# Slave.net
KiCad netlist of a schematic drawn in Altium Designer
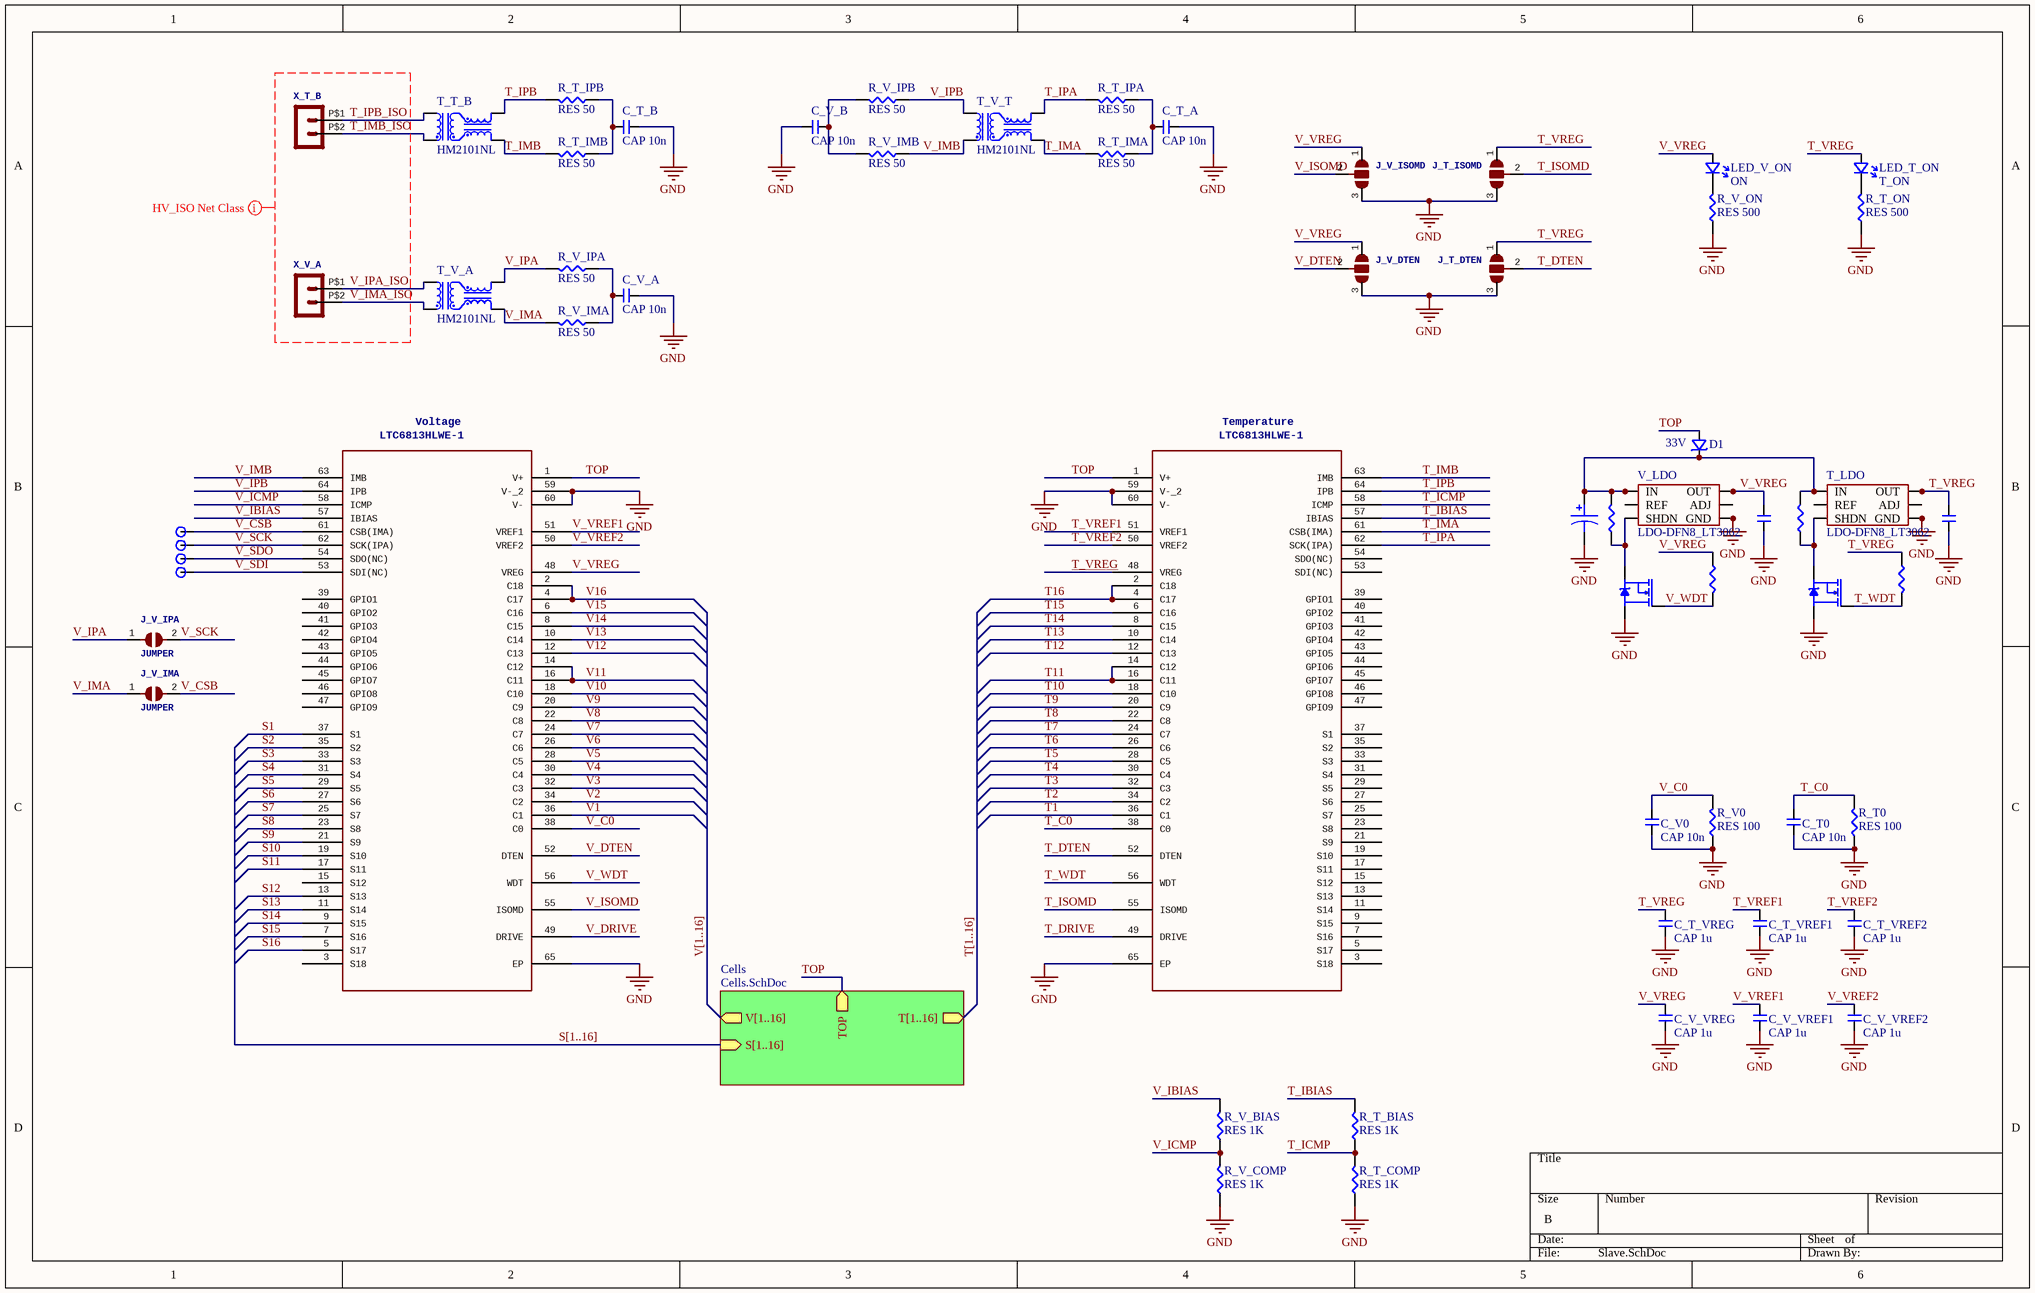
[diagram p0: Slave.SchDoc]

(export (version "E")
  (design (tool "Eeschema 10.0.6"))
  (components
    (comp (ref "CAP-T_VREG")
      (value "10uF")
      (footprint "CAP-0603")
      (libsource (lib "ife19_Elec_Library") (part "CAP-0603"))
    )
    (comp (ref "CAP-V_VREG")
      (value "10uF")
      (footprint "CAP-0603")
      (libsource (lib "ife19_Elec_Library") (part "CAP-0603"))
    )
    (comp (ref "CAP_TOP")
      (value "10uF")
      (footprint "CAP-6.3D7.7H-SMD")
      (libsource (lib "ife19_Elec_Library") (part "CAP-6.3D7.7H-SMD"))
    )
    (comp (ref "C_T0")
      (value "CAP 10n")
      (footprint "CAP-0603")
      (description "CAP-0603")
      (libsource (lib "altium-import") (part "root_1_CAP-0603_"))
    )
    (comp (ref "C_T_A")
      (value "CAP 10n")
      (footprint "CAP-0603")
      (description "CAP-0603")
      (libsource (lib "ife18_TS_BMS_LTC6813_v2_Library") (part "CAP-0603"))
    )
    (comp (ref "C_T_B")
      (value "CAP 10n")
      (footprint "CAP-0603")
      (description "CAP-0603")
      (libsource (lib "ife18_TS_BMS_LTC6813_v2_Library") (part "CAP-0603"))
    )
    (comp (ref "C_T_VREF1")
      (value "CAP 1u")
      (footprint "CAP-0603")
      (description "CAP-0603")
      (libsource (lib "altium-import") (part "root_1_CAP-0603_"))
    )
    (comp (ref "C_T_VREF2")
      (value "CAP 1u")
      (footprint "CAP-0603")
      (description "CAP-0603")
      (libsource (lib "altium-import") (part "root_1_CAP-0603_"))
    )
    (comp (ref "C_T_VREG")
      (value "CAP 1u")
      (footprint "CAP-0603")
      (description "CAP-0603")
      (libsource (lib "altium-import") (part "root_1_CAP-0603_"))
    )
    (comp (ref "C_V0")
      (value "CAP 10n")
      (footprint "CAP-0603")
      (description "CAP-0603")
      (libsource (lib "altium-import") (part "root_1_CAP-0603_"))
    )
    (comp (ref "C_V_A")
      (value "CAP 10n")
      (footprint "CAP-0603")
      (description "CAP-0603")
      (libsource (lib "ife18_TS_BMS_LTC6813_v2_Library") (part "CAP-0603"))
    )
    (comp (ref "C_V_B")
      (value "CAP 10n")
      (footprint "CAP-0603")
      (description "CAP-0603")
      (libsource (lib "ife18_TS_BMS_LTC6813_v2_Library") (part "CAP-0603"))
    )
    (comp (ref "C_V_VREF1")
      (value "CAP 1u")
      (footprint "CAP-0603")
      (description "CAP-0603")
      (libsource (lib "altium-import") (part "root_1_CAP-0603_"))
    )
    (comp (ref "C_V_VREF2")
      (value "CAP 1u")
      (footprint "CAP-0603")
      (description "CAP-0603")
      (libsource (lib "altium-import") (part "root_1_CAP-0603_"))
    )
    (comp (ref "C_V_VREG")
      (value "CAP 1u")
      (footprint "CAP-0603")
      (description "CAP-0603")
      (libsource (lib "altium-import") (part "root_1_CAP-0603_"))
    )
    (comp (ref "D1")
      (value "33V")
      (footprint "SMB")
      (libsource (lib "ife19_Elec_Library") (part "DIODE-SMB"))
    )
    (comp (ref "J_T_DTEN")
      (value "~")
      (footprint "SJ_2")
      (description "JUMPER_2W")
      (libsource (lib "") (part "JUMPER_2W_1"))
    )
    (comp (ref "J_T_ISOMD")
      (value "~")
      (footprint "SJ_2")
      (description "JUMPER_2W")
      (libsource (lib "") (part "JUMPER_2W_1"))
    )
    (comp (ref "J_V_DTEN")
      (value "~")
      (footprint "SJ_2")
      (description "JUMPER_2W")
      (libsource (lib "IFE_Jumpers") (part "JUMPER_2W"))
    )
    (comp (ref "J_V_IMA")
      (value "JUMPER")
      (footprint "SJ")
      (libsource (lib "altium-import") (part "root_0_JUMPER_"))
    )
    (comp (ref "J_V_IPA")
      (value "JUMPER")
      (footprint "SJ")
      (libsource (lib "altium-import") (part "root_0_JUMPER_"))
    )
    (comp (ref "J_V_ISOMD")
      (value "~")
      (footprint "SJ_2")
      (description "JUMPER_2W")
      (libsource (lib "IFE_Jumpers") (part "JUMPER_2W"))
    )
    (comp (ref "LED_T_ON")
      (value "T_ON")
      (footprint "LED-0603")
      (description "LED-0603")
      (libsource (lib "altium-import") (part "root_3_LED-0603_"))
    )
    (comp (ref "LED_V_ON")
      (value "ON")
      (footprint "LED-0603")
      (description "LED-0603")
      (libsource (lib "altium-import") (part "root_3_LED-0603_"))
    )
    (comp (ref "R_T0")
      (value "RES 100")
      (footprint "RES-0603")
      (libsource (lib "altium-import") (part "root_1_RES-0603_"))
    )
    (comp (ref "R_T_BIAS")
      (value "RES 1K")
      (footprint "RES-0603")
      (libsource (lib "altium-import") (part "root_1_RES-0603_"))
    )
    (comp (ref "R_T_COMP")
      (value "RES 1K")
      (footprint "RES-0603")
      (libsource (lib "altium-import") (part "root_1_RES-0603_"))
    )
    (comp (ref "R_T_IMA")
      (value "RES 50")
      (footprint "RES-0603")
      (libsource (lib "ife18_TS_BMS_LTC6813_v2_Library") (part "RES-0603"))
    )
    (comp (ref "R_T_IMB")
      (value "RES 50")
      (footprint "RES-0603")
      (libsource (lib "ife18_TS_BMS_LTC6813_v2_Library") (part "RES-0603"))
    )
    (comp (ref "R_T_IPA")
      (value "RES 50")
      (footprint "RES-0603")
      (libsource (lib "ife18_TS_BMS_LTC6813_v2_Library") (part "RES-0603"))
    )
    (comp (ref "R_T_IPB")
      (value "RES 50")
      (footprint "RES-0603")
      (libsource (lib "ife18_TS_BMS_LTC6813_v2_Library") (part "RES-0603"))
    )
    (comp (ref "R_T_ON")
      (value "RES 500")
      (footprint "RES-0603")
      (libsource (lib "altium-import") (part "root_1_RES-0603_"))
    )
    (comp (ref "R_V0")
      (value "RES 100")
      (footprint "RES-0603")
      (libsource (lib "altium-import") (part "root_1_RES-0603_"))
    )
    (comp (ref "R_V_BIAS")
      (value "RES 1K")
      (footprint "RES-0603")
      (libsource (lib "altium-import") (part "root_1_RES-0603_"))
    )
    (comp (ref "R_V_COMP")
      (value "RES 1K")
      (footprint "RES-0603")
      (libsource (lib "altium-import") (part "root_1_RES-0603_"))
    )
    (comp (ref "R_V_IMA")
      (value "RES 50")
      (footprint "RES-0603")
      (libsource (lib "ife18_TS_BMS_LTC6813_v2_Library") (part "RES-0603"))
    )
    (comp (ref "R_V_IMB")
      (value "RES 50")
      (footprint "RES-0603")
      (libsource (lib "ife18_TS_BMS_LTC6813_v2_Library") (part "RES-0603"))
    )
    (comp (ref "R_V_IPA")
      (value "RES 50")
      (footprint "RES-0603")
      (libsource (lib "ife18_TS_BMS_LTC6813_v2_Library") (part "RES-0603"))
    )
    (comp (ref "R_V_IPB")
      (value "RES 50")
      (footprint "RES-0603")
      (libsource (lib "ife18_TS_BMS_LTC6813_v2_Library") (part "RES-0603"))
    )
    (comp (ref "R_V_ON")
      (value "RES 500")
      (footprint "RES-0603")
      (libsource (lib "altium-import") (part "root_1_RES-0603_"))
    )
    (comp (ref "Temperature")
      (value "LTC6813HLWE-1")
      (footprint "LQFP64_LWE_A")
      (fields (field (name "LIBRARYNAME") "LTC6813_Official"))
      (libsource (lib "altium-import") (part "root_0_LTC6813HLWE-1_"))
    )
    (comp (ref "TP_CSB")
      (value "S")
      (footprint "Testpoint")
      (libsource (lib "altium-import") (part "root_0_Testpoint_"))
    )
    (comp (ref "TP_SCK")
      (value "C")
      (footprint "Testpoint")
      (libsource (lib "altium-import") (part "root_0_Testpoint_"))
    )
    (comp (ref "TP_SDI")
      (value "I")
      (footprint "Testpoint")
      (libsource (lib "altium-import") (part "root_0_Testpoint_"))
    )
    (comp (ref "TP_SDO")
      (value "O")
      (footprint "Testpoint")
      (libsource (lib "altium-import") (part "root_0_Testpoint_"))
    )
    (comp (ref "T_LDO")
      (value "LDO-DFN8_LT3062")
      (footprint "DFN8")
      (libsource (lib "ife19_Elec_Library") (part "LDO-DFN8_LT3062"))
    )
    (comp (ref "T_LDO_NMOS")
      (value "NMOS-SOT23")
      (footprint "SOT23")
      (libsource (lib "ife19_Elec_Library") (part "NMOS-SOT23"))
    )
    (comp (ref "T_LDO_NMOS_PU")
      (value "100K")
      (footprint "RES-0603")
      (libsource (lib "ife19_Elec_Library") (part "RES-0603"))
    )
    (comp (ref "T_LDO_PU")
      (value "10K")
      (footprint "RES-0603")
      (libsource (lib "ife19_Elec_Library") (part "RES-0603"))
    )
    (comp (ref "T_T_B")
      (value "HM2101NL")
      (footprint "HM2101")
      (libsource (lib "altium-import") (part "root_2_HM2101NL_"))
    )
    (comp (ref "T_V_A")
      (value "HM2101NL")
      (footprint "HM2101")
      (libsource (lib "altium-import") (part "root_2_HM2101NL_"))
    )
    (comp (ref "T_V_T")
      (value "HM2101NL")
      (footprint "HM2101")
      (libsource (lib "altium-import") (part "root_2_HM2101NL_"))
    )
    (comp (ref "Voltage")
      (value "LTC6813HLWE-1")
      (footprint "LQFP64_LWE_A")
      (fields (field (name "LIBRARYNAME") "LTC6813_Official"))
      (libsource (lib "altium-import") (part "root_0_mirrored_LTC6813HLWE-1_"))
    )
    (comp (ref "V_LDO")
      (value "LDO-DFN8_LT3062")
      (footprint "DFN8")
      (libsource (lib "ife19_Elec_Library") (part "LDO-DFN8_LT3062"))
    )
    (comp (ref "V_LDO_NMOS")
      (value "NMOS-SOT23")
      (footprint "SOT23")
      (libsource (lib "ife19_Elec_Library") (part "NMOS-SOT23"))
    )
    (comp (ref "V_LDO_NMOS_PU")
      (value "100K")
      (footprint "RES-0603")
      (libsource (lib "ife19_Elec_Library") (part "RES-0603"))
    )
    (comp (ref "V_LDO_PU")
      (value "10K")
      (footprint "RES-0603")
      (libsource (lib "ife19_Elec_Library") (part "RES-0603"))
    )
    (comp (ref "X_T_B")
      (value "Molex - Micro-Fit 3.0 Series connector,  3.00mm (0.118\") pitch header, 2 positions.")
      (footprint "43650-0224")
      (libsource (lib "altium-import") (part "root_0_mirrored_HEADER_POS2_?43650-0224_"))
    )
    (comp (ref "X_V_A")
      (value "Molex - Micro-Fit 3.0 Series connector,  3.00mm (0.118\") pitch header, 2 positions.")
      (footprint "43650-0224")
      (libsource (lib "altium-import") (part "root_0_mirrored_HEADER_POS2_?43650-0224_"))
    )
  )
  (nets
    (net (code "1") (name "/S1") (class "Default")
      (node (ref "Voltage") (pin "37") (pinfunction "S1_37") (pintype "passive"))
    )
    (net (code "2") (name "/S2") (class "Default")
      (node (ref "Voltage") (pin "35") (pinfunction "S2_35") (pintype "passive"))
    )
    (net (code "3") (name "/S3") (class "Default")
      (node (ref "Voltage") (pin "33") (pinfunction "S3_33") (pintype "passive"))
    )
    (net (code "4") (name "/S4") (class "Default")
      (node (ref "Voltage") (pin "31") (pinfunction "S4_31") (pintype "passive"))
    )
    (net (code "5") (name "/S5") (class "Default")
      (node (ref "Voltage") (pin "29") (pinfunction "S5_29") (pintype "passive"))
    )
    (net (code "6") (name "/S6") (class "Default")
      (node (ref "Voltage") (pin "27") (pinfunction "S6_27") (pintype "passive"))
    )
    (net (code "7") (name "/S7") (class "Default")
      (node (ref "Voltage") (pin "25") (pinfunction "S7_25") (pintype "passive"))
    )
    (net (code "8") (name "/S8") (class "Default")
      (node (ref "Voltage") (pin "23") (pinfunction "S8_23") (pintype "passive"))
    )
    (net (code "9") (name "/S9") (class "Default")
      (node (ref "Voltage") (pin "21") (pinfunction "S9_21") (pintype "passive"))
    )
    (net (code "10") (name "/S10") (class "Default")
      (node (ref "Voltage") (pin "19") (pinfunction "S10_19") (pintype "passive"))
    )
    (net (code "11") (name "/S11") (class "Default")
      (node (ref "Voltage") (pin "17") (pinfunction "S11_17") (pintype "passive"))
    )
    (net (code "12") (name "/S12") (class "Default")
      (node (ref "Voltage") (pin "13") (pinfunction "S13_13") (pintype "passive"))
    )
    (net (code "13") (name "/S13") (class "Default")
      (node (ref "Voltage") (pin "11") (pinfunction "S14_11") (pintype "passive"))
    )
    (net (code "14") (name "/S14") (class "Default")
      (node (ref "Voltage") (pin "9") (pinfunction "S15_9") (pintype "passive"))
    )
    (net (code "15") (name "/S15") (class "Default")
      (node (ref "Voltage") (pin "7") (pinfunction "S16_7") (pintype "passive"))
    )
    (net (code "16") (name "/S16") (class "Default")
      (node (ref "Voltage") (pin "5") (pinfunction "S17_5") (pintype "passive"))
    )
    (net (code "18") (name "/T1") (class "Default")
      (node (ref "Temperature") (pin "36") (pinfunction "C1_36") (pintype "passive"))
    )
    (net (code "19") (name "/T2") (class "Default")
      (node (ref "Temperature") (pin "34") (pinfunction "C2_34") (pintype "passive"))
    )
    (net (code "20") (name "/T3") (class "Default")
      (node (ref "Temperature") (pin "32") (pinfunction "C3_32") (pintype "passive"))
    )
    (net (code "21") (name "/T4") (class "Default")
      (node (ref "Temperature") (pin "30") (pinfunction "C4_30") (pintype "passive"))
    )
    (net (code "22") (name "/T5") (class "Default")
      (node (ref "Temperature") (pin "28") (pinfunction "C5_28") (pintype "passive"))
    )
    (net (code "23") (name "/T6") (class "Default")
      (node (ref "Temperature") (pin "26") (pinfunction "C6_26") (pintype "passive"))
    )
    (net (code "24") (name "/T7") (class "Default")
      (node (ref "Temperature") (pin "24") (pinfunction "C7_24") (pintype "passive"))
    )
    (net (code "25") (name "/T8") (class "Default")
      (node (ref "Temperature") (pin "22") (pinfunction "C8_22") (pintype "passive"))
    )
    (net (code "26") (name "/T9") (class "Default")
      (node (ref "Temperature") (pin "20") (pinfunction "C9_20") (pintype "passive"))
    )
    (net (code "27") (name "/T10") (class "Default")
      (node (ref "Temperature") (pin "18") (pinfunction "C10_18") (pintype "passive"))
    )
    (net (code "28") (name "/T11") (class "Default")
      (node (ref "Temperature") (pin "14") (pinfunction "C12_14") (pintype "passive"))
      (node (ref "Temperature") (pin "16") (pinfunction "C11_16") (pintype "passive"))
    )
    (net (code "29") (name "/T12") (class "Default")
      (node (ref "Temperature") (pin "12") (pinfunction "C13_12") (pintype "passive"))
    )
    (net (code "30") (name "/T13") (class "Default")
      (node (ref "Temperature") (pin "10") (pinfunction "C14_10") (pintype "passive"))
    )
    (net (code "31") (name "/T14") (class "Default")
      (node (ref "Temperature") (pin "8") (pinfunction "C15_8") (pintype "passive"))
    )
    (net (code "32") (name "/T15") (class "Default")
      (node (ref "Temperature") (pin "6") (pinfunction "C16_6") (pintype "passive"))
    )
    (net (code "33") (name "/T16") (class "Default")
      (node (ref "Temperature") (pin "2") (pinfunction "C18_2") (pintype "passive"))
      (node (ref "Temperature") (pin "4") (pinfunction "C17_4") (pintype "passive"))
    )
    (net (code "34") (name "/TOP") (class "Default")
      (node (ref "D1") (pin "A") (pinfunction "A_A") (pintype "passive"))
      (node (ref "Temperature") (pin "1") (pinfunction "V+_1") (pintype "passive"))
      (node (ref "Voltage") (pin "1") (pinfunction "V+_1") (pintype "passive"))
    )
    (net (code "36") (name "/T_C0") (class "Default")
      (node (ref "C_T0") (pin "2") (pinfunction "2_2") (pintype "passive"))
      (node (ref "R_T0") (pin "2") (pinfunction "2_2") (pintype "passive"))
      (node (ref "Temperature") (pin "38") (pinfunction "C0_38") (pintype "passive"))
    )
    (net (code "37") (name "/T_DRIVE") (class "Default")
      (node (ref "Temperature") (pin "49") (pinfunction "DRIVE_49") (pintype "passive"))
    )
    (net (code "38") (name "/T_DTEN") (class "Default")
      (node (ref "J_T_DTEN") (pin "2") (pinfunction "2_2") (pintype "passive"))
      (node (ref "Temperature") (pin "52") (pinfunction "DTEN_52") (pintype "passive"))
    )
    (net (code "39") (name "/T_IBIAS") (class "Default")
      (node (ref "R_T_BIAS") (pin "2") (pinfunction "2_2") (pintype "passive"))
      (node (ref "Temperature") (pin "57") (pinfunction "IBIAS_57") (pintype "passive"))
    )
    (net (code "40") (name "/T_ICMP") (class "Default")
      (node (ref "R_T_BIAS") (pin "1") (pinfunction "1_1") (pintype "passive"))
      (node (ref "R_T_COMP") (pin "2") (pinfunction "2_2") (pintype "passive"))
      (node (ref "Temperature") (pin "58") (pinfunction "ICMP_58") (pintype "passive"))
    )
    (net (code "41") (name "/T_IMA") (class "Default")
      (node (ref "R_T_IMA") (pin "2") (pinfunction "2_2") (pintype "passive"))
      (node (ref "T_V_T") (pin "4") (pinfunction "4_4") (pintype "passive"))
      (node (ref "Temperature") (pin "61") (pinfunction "CSB(IMA)_61") (pintype "passive"))
    )
    (net (code "42") (name "/T_IMB") (class "Default")
      (node (ref "R_T_IMB") (pin "2") (pinfunction "2_2") (pintype "passive"))
      (node (ref "T_T_B") (pin "4") (pinfunction "4_4") (pintype "passive"))
      (node (ref "Temperature") (pin "63") (pinfunction "IMB_63") (pintype "passive"))
    )
    (net (code "43") (name "/T_IMB_ISO") (class "Default")
      (node (ref "T_T_B") (pin "3") (pinfunction "3_3") (pintype "passive"))
      (node (ref "X_T_B") (pin "P$2") (pinfunction "2_P$2") (pintype "passive"))
    )
    (net (code "44") (name "/T_IPA") (class "Default")
      (node (ref "R_T_IPA") (pin "2") (pinfunction "2_2") (pintype "passive"))
      (node (ref "T_V_T") (pin "6") (pinfunction "6_6") (pintype "passive"))
      (node (ref "Temperature") (pin "62") (pinfunction "SCK(IPA)_62") (pintype "passive"))
    )
    (net (code "45") (name "/T_IPB") (class "Default")
      (node (ref "R_T_IPB") (pin "2") (pinfunction "2_2") (pintype "passive"))
      (node (ref "T_T_B") (pin "6") (pinfunction "6_6") (pintype "passive"))
      (node (ref "Temperature") (pin "64") (pinfunction "IPB_64") (pintype "passive"))
    )
    (net (code "46") (name "/T_IPB_ISO") (class "Default")
      (node (ref "T_T_B") (pin "1") (pinfunction "1_1") (pintype "passive"))
      (node (ref "X_T_B") (pin "P$1") (pinfunction "1_P$1") (pintype "passive"))
    )
    (net (code "47") (name "/T_ISOMD") (class "Default")
      (node (ref "J_T_ISOMD") (pin "2") (pinfunction "2_2") (pintype "passive"))
      (node (ref "Temperature") (pin "55") (pinfunction "ISOMD_55") (pintype "passive"))
    )
    (net (code "48") (name "/T_VREF1") (class "Default")
      (node (ref "C_T_VREF1") (pin "2") (pinfunction "2_2") (pintype "passive"))
      (node (ref "Temperature") (pin "51") (pinfunction "VREF1_51") (pintype "passive"))
    )
    (net (code "49") (name "/T_VREF2") (class "Default")
      (node (ref "C_T_VREF2") (pin "2") (pinfunction "2_2") (pintype "passive"))
      (node (ref "Temperature") (pin "50") (pinfunction "VREF2_50") (pintype "passive"))
    )
    (net (code "50") (name "/T_VREG") (class "Default")
      (node (ref "CAP-T_VREG") (pin "2") (pinfunction "2_2") (pintype "passive"))
      (node (ref "C_T_VREG") (pin "2") (pinfunction "2_2") (pintype "passive"))
      (node (ref "J_T_DTEN") (pin "1") (pinfunction "1_1") (pintype "passive"))
      (node (ref "J_T_ISOMD") (pin "1") (pinfunction "1_1") (pintype "passive"))
      (node (ref "LED_T_ON") (pin "A") (pinfunction "A_A") (pintype "passive"))
      (node (ref "T_LDO") (pin "3") (pinfunction "OUT_3") (pintype "passive"))
      (node (ref "T_LDO") (pin "4") (pinfunction "OUT_4") (pintype "passive"))
      (node (ref "T_LDO_NMOS_PU") (pin "1") (pinfunction "1_1") (pintype "passive"))
      (node (ref "Temperature") (pin "48") (pinfunction "VREG_48") (pintype "passive"))
    )
    (net (code "51") (name "/T_WDT") (class "Default")
      (node (ref "T_LDO_NMOS") (pin "1") (pinfunction "G_1") (pintype "passive"))
      (node (ref "T_LDO_NMOS_PU") (pin "2") (pinfunction "2_2") (pintype "passive"))
      (node (ref "Temperature") (pin "56") (pinfunction "WDT_56") (pintype "passive"))
    )
    (net (code "52") (name "/V1") (class "Default")
      (node (ref "Voltage") (pin "36") (pinfunction "C1_36") (pintype "passive"))
    )
    (net (code "53") (name "/V2") (class "Default")
      (node (ref "Voltage") (pin "34") (pinfunction "C2_34") (pintype "passive"))
    )
    (net (code "54") (name "/V3") (class "Default")
      (node (ref "Voltage") (pin "32") (pinfunction "C3_32") (pintype "passive"))
    )
    (net (code "55") (name "/V4") (class "Default")
      (node (ref "Voltage") (pin "30") (pinfunction "C4_30") (pintype "passive"))
    )
    (net (code "56") (name "/V5") (class "Default")
      (node (ref "Voltage") (pin "28") (pinfunction "C5_28") (pintype "passive"))
    )
    (net (code "57") (name "/V6") (class "Default")
      (node (ref "Voltage") (pin "26") (pinfunction "C6_26") (pintype "passive"))
    )
    (net (code "58") (name "/V7") (class "Default")
      (node (ref "Voltage") (pin "24") (pinfunction "C7_24") (pintype "passive"))
    )
    (net (code "59") (name "/V8") (class "Default")
      (node (ref "Voltage") (pin "22") (pinfunction "C8_22") (pintype "passive"))
    )
    (net (code "60") (name "/V9") (class "Default")
      (node (ref "Voltage") (pin "20") (pinfunction "C9_20") (pintype "passive"))
    )
    (net (code "61") (name "/V10") (class "Default")
      (node (ref "Voltage") (pin "18") (pinfunction "C10_18") (pintype "passive"))
    )
    (net (code "62") (name "/V11") (class "Default")
      (node (ref "Voltage") (pin "14") (pinfunction "C12_14") (pintype "passive"))
      (node (ref "Voltage") (pin "16") (pinfunction "C11_16") (pintype "passive"))
    )
    (net (code "63") (name "/V12") (class "Default")
      (node (ref "Voltage") (pin "12") (pinfunction "C13_12") (pintype "passive"))
    )
    (net (code "64") (name "/V13") (class "Default")
      (node (ref "Voltage") (pin "10") (pinfunction "C14_10") (pintype "passive"))
    )
    (net (code "65") (name "/V14") (class "Default")
      (node (ref "Voltage") (pin "8") (pinfunction "C15_8") (pintype "passive"))
    )
    (net (code "66") (name "/V15") (class "Default")
      (node (ref "Voltage") (pin "6") (pinfunction "C16_6") (pintype "passive"))
    )
    (net (code "67") (name "/V16") (class "Default")
      (node (ref "Voltage") (pin "2") (pinfunction "C18_2") (pintype "passive"))
      (node (ref "Voltage") (pin "4") (pinfunction "C17_4") (pintype "passive"))
    )
    (net (code "69") (name "/V_C0") (class "Default")
      (node (ref "C_V0") (pin "2") (pinfunction "2_2") (pintype "passive"))
      (node (ref "R_V0") (pin "2") (pinfunction "2_2") (pintype "passive"))
      (node (ref "Voltage") (pin "38") (pinfunction "C0_38") (pintype "passive"))
    )
    (net (code "70") (name "/V_CSB") (class "Default")
      (node (ref "J_V_IMA") (pin "2") (pinfunction "2_2") (pintype "passive"))
      (node (ref "TP_CSB") (pin "1") (pinfunction "1_1") (pintype "passive"))
      (node (ref "Voltage") (pin "61") (pinfunction "CSB(IMA)_61") (pintype "passive"))
    )
    (net (code "71") (name "/V_DRIVE") (class "Default")
      (node (ref "Voltage") (pin "49") (pinfunction "DRIVE_49") (pintype "passive"))
    )
    (net (code "72") (name "/V_DTEN") (class "Default")
      (node (ref "J_V_DTEN") (pin "2") (pinfunction "2_2") (pintype "passive"))
      (node (ref "Voltage") (pin "52") (pinfunction "DTEN_52") (pintype "passive"))
    )
    (net (code "73") (name "/V_IBIAS") (class "Default")
      (node (ref "R_V_BIAS") (pin "2") (pinfunction "2_2") (pintype "passive"))
      (node (ref "Voltage") (pin "57") (pinfunction "IBIAS_57") (pintype "passive"))
    )
    (net (code "74") (name "/V_ICMP") (class "Default")
      (node (ref "R_V_BIAS") (pin "1") (pinfunction "1_1") (pintype "passive"))
      (node (ref "R_V_COMP") (pin "2") (pinfunction "2_2") (pintype "passive"))
      (node (ref "Voltage") (pin "58") (pinfunction "ICMP_58") (pintype "passive"))
    )
    (net (code "75") (name "/V_IMA") (class "Default")
      (node (ref "J_V_IMA") (pin "1") (pinfunction "1_1") (pintype "passive"))
      (node (ref "R_V_IMA") (pin "2") (pinfunction "2_2") (pintype "passive"))
      (node (ref "T_V_A") (pin "4") (pinfunction "4_4") (pintype "passive"))
    )
    (net (code "76") (name "/V_IMA_ISO") (class "Default")
      (node (ref "T_V_A") (pin "3") (pinfunction "3_3") (pintype "passive"))
      (node (ref "X_V_A") (pin "P$2") (pinfunction "2_P$2") (pintype "passive"))
    )
    (net (code "77") (name "/V_IMB") (class "Default")
      (node (ref "R_V_IMB") (pin "2") (pinfunction "2_2") (pintype "passive"))
      (node (ref "T_V_T") (pin "3") (pinfunction "3_3") (pintype "passive"))
      (node (ref "Voltage") (pin "63") (pinfunction "IMB_63") (pintype "passive"))
    )
    (net (code "78") (name "/V_IPA") (class "Default")
      (node (ref "J_V_IPA") (pin "1") (pinfunction "1_1") (pintype "passive"))
      (node (ref "R_V_IPA") (pin "2") (pinfunction "2_2") (pintype "passive"))
      (node (ref "T_V_A") (pin "6") (pinfunction "6_6") (pintype "passive"))
    )
    (net (code "79") (name "/V_IPA_ISO") (class "Default")
      (node (ref "T_V_A") (pin "1") (pinfunction "1_1") (pintype "passive"))
      (node (ref "X_V_A") (pin "P$1") (pinfunction "1_P$1") (pintype "passive"))
    )
    (net (code "80") (name "/V_IPB") (class "Default")
      (node (ref "R_V_IPB") (pin "2") (pinfunction "2_2") (pintype "passive"))
      (node (ref "T_V_T") (pin "1") (pinfunction "1_1") (pintype "passive"))
      (node (ref "Voltage") (pin "64") (pinfunction "IPB_64") (pintype "passive"))
    )
    (net (code "81") (name "/V_ISOMD") (class "Default")
      (node (ref "J_V_ISOMD") (pin "2") (pinfunction "2_2") (pintype "passive"))
      (node (ref "Voltage") (pin "55") (pinfunction "ISOMD_55") (pintype "passive"))
    )
    (net (code "82") (name "/V_SCK") (class "Default")
      (node (ref "J_V_IPA") (pin "2") (pinfunction "2_2") (pintype "passive"))
      (node (ref "TP_SCK") (pin "1") (pinfunction "1_1") (pintype "passive"))
      (node (ref "Voltage") (pin "62") (pinfunction "SCK(IPA)_62") (pintype "passive"))
    )
    (net (code "83") (name "/V_SDI") (class "Default")
      (node (ref "TP_SDI") (pin "1") (pinfunction "1_1") (pintype "passive"))
      (node (ref "Voltage") (pin "53") (pinfunction "SDI(NC)_53") (pintype "passive"))
    )
    (net (code "84") (name "/V_SDO") (class "Default")
      (node (ref "TP_SDO") (pin "1") (pinfunction "1_1") (pintype "passive"))
      (node (ref "Voltage") (pin "54") (pinfunction "SDO(NC)_54") (pintype "passive"))
    )
    (net (code "85") (name "/V_VREF1") (class "Default")
      (node (ref "C_V_VREF1") (pin "2") (pinfunction "2_2") (pintype "passive"))
      (node (ref "Voltage") (pin "51") (pinfunction "VREF1_51") (pintype "passive"))
    )
    (net (code "86") (name "/V_VREF2") (class "Default")
      (node (ref "C_V_VREF2") (pin "2") (pinfunction "2_2") (pintype "passive"))
      (node (ref "Voltage") (pin "50") (pinfunction "VREF2_50") (pintype "passive"))
    )
    (net (code "87") (name "/V_VREG") (class "Default")
      (node (ref "CAP-V_VREG") (pin "2") (pinfunction "2_2") (pintype "passive"))
      (node (ref "C_V_VREG") (pin "2") (pinfunction "2_2") (pintype "passive"))
      (node (ref "J_V_DTEN") (pin "1") (pinfunction "1_1") (pintype "passive"))
      (node (ref "J_V_ISOMD") (pin "1") (pinfunction "1_1") (pintype "passive"))
      (node (ref "LED_V_ON") (pin "A") (pinfunction "A_A") (pintype "passive"))
      (node (ref "V_LDO") (pin "3") (pinfunction "OUT_3") (pintype "passive"))
      (node (ref "V_LDO") (pin "4") (pinfunction "OUT_4") (pintype "passive"))
      (node (ref "V_LDO_NMOS_PU") (pin "1") (pinfunction "1_1") (pintype "passive"))
      (node (ref "Voltage") (pin "48") (pinfunction "VREG_48") (pintype "passive"))
    )
    (net (code "88") (name "/V_WDT") (class "Default")
      (node (ref "V_LDO_NMOS") (pin "1") (pinfunction "G_1") (pintype "passive"))
      (node (ref "V_LDO_NMOS_PU") (pin "2") (pinfunction "2_2") (pintype "passive"))
      (node (ref "Voltage") (pin "56") (pinfunction "WDT_56") (pintype "passive"))
    )
    (net (code "89") (name "GND") (class "Default")
      (node (ref "CAP-T_VREG") (pin "1") (pinfunction "1_1") (pintype "passive"))
      (node (ref "CAP-V_VREG") (pin "1") (pinfunction "1_1") (pintype "passive"))
      (node (ref "CAP_TOP") (pin "NEG") (pinfunction "-_NEG") (pintype "passive"))
      (node (ref "C_T0") (pin "1") (pinfunction "1_1") (pintype "passive"))
      (node (ref "C_T_A") (pin "1") (pinfunction "1_1") (pintype "passive"))
      (node (ref "C_T_B") (pin "1") (pinfunction "1_1") (pintype "passive"))
      (node (ref "C_T_VREF1") (pin "1") (pinfunction "1_1") (pintype "passive"))
      (node (ref "C_T_VREF2") (pin "1") (pinfunction "1_1") (pintype "passive"))
      (node (ref "C_T_VREG") (pin "1") (pinfunction "1_1") (pintype "passive"))
      (node (ref "C_V0") (pin "1") (pinfunction "1_1") (pintype "passive"))
      (node (ref "C_V_A") (pin "1") (pinfunction "1_1") (pintype "passive"))
      (node (ref "C_V_B") (pin "1") (pinfunction "1_1") (pintype "passive"))
      (node (ref "C_V_VREF1") (pin "1") (pinfunction "1_1") (pintype "passive"))
      (node (ref "C_V_VREF2") (pin "1") (pinfunction "1_1") (pintype "passive"))
      (node (ref "C_V_VREG") (pin "1") (pinfunction "1_1") (pintype "passive"))
      (node (ref "J_T_DTEN") (pin "3") (pinfunction "3_3") (pintype "passive"))
      (node (ref "J_T_ISOMD") (pin "3") (pinfunction "3_3") (pintype "passive"))
      (node (ref "J_V_DTEN") (pin "3") (pinfunction "3_3") (pintype "passive"))
      (node (ref "J_V_ISOMD") (pin "3") (pinfunction "3_3") (pintype "passive"))
      (node (ref "R_T0") (pin "1") (pinfunction "1_1") (pintype "passive"))
      (node (ref "R_T_COMP") (pin "1") (pinfunction "1_1") (pintype "passive"))
      (node (ref "R_T_ON") (pin "1") (pinfunction "1_1") (pintype "passive"))
      (node (ref "R_V0") (pin "1") (pinfunction "1_1") (pintype "passive"))
      (node (ref "R_V_COMP") (pin "1") (pinfunction "1_1") (pintype "passive"))
      (node (ref "R_V_ON") (pin "1") (pinfunction "1_1") (pintype "passive"))
      (node (ref "T_LDO") (pin "8") (pinfunction "GND_8") (pintype "passive"))
      (node (ref "T_LDO") (pin "EP") (pinfunction "GND_EP") (pintype "passive"))
      (node (ref "T_LDO_NMOS") (pin "2") (pinfunction "S_2") (pintype "passive"))
      (node (ref "Temperature") (pin "59") (pinfunction "V-_2_59") (pintype "passive"))
      (node (ref "Temperature") (pin "60") (pinfunction "V-_60") (pintype "passive"))
      (node (ref "Temperature") (pin "65") (pinfunction "EP_65") (pintype "passive"))
      (node (ref "V_LDO") (pin "8") (pinfunction "GND_8") (pintype "passive"))
      (node (ref "V_LDO") (pin "EP") (pinfunction "GND_EP") (pintype "passive"))
      (node (ref "V_LDO_NMOS") (pin "2") (pinfunction "S_2") (pintype "passive"))
      (node (ref "Voltage") (pin "59") (pinfunction "V-_2_59") (pintype "passive"))
      (node (ref "Voltage") (pin "60") (pinfunction "V-_60") (pintype "passive"))
      (node (ref "Voltage") (pin "65") (pinfunction "EP_65") (pintype "passive"))
    )
    (net (code "90") (name "Net-(CAP_TOP-+)") (class "Default")
      (node (ref "CAP_TOP") (pin "POS") (pinfunction "+_POS") (pintype "passive"))
      (node (ref "D1") (pin "K") (pinfunction "K_K") (pintype "passive"))
      (node (ref "T_LDO") (pin "5") (pinfunction "IN_5") (pintype "passive"))
      (node (ref "T_LDO") (pin "6") (pinfunction "IN_6") (pintype "passive"))
      (node (ref "T_LDO_PU") (pin "2") (pinfunction "2_2") (pintype "passive"))
      (node (ref "V_LDO") (pin "5") (pinfunction "IN_5") (pintype "passive"))
      (node (ref "V_LDO") (pin "6") (pinfunction "IN_6") (pintype "passive"))
      (node (ref "V_LDO_PU") (pin "2") (pinfunction "2_2") (pintype "passive"))
    )
    (net (code "91") (name "Net-(C_T_A-Pad2)") (class "Default")
      (node (ref "C_T_A") (pin "2") (pinfunction "2_2") (pintype "passive"))
      (node (ref "R_T_IMA") (pin "1") (pinfunction "1_1") (pintype "passive"))
      (node (ref "R_T_IPA") (pin "1") (pinfunction "1_1") (pintype "passive"))
    )
    (net (code "92") (name "Net-(C_T_B-Pad2)") (class "Default")
      (node (ref "C_T_B") (pin "2") (pinfunction "2_2") (pintype "passive"))
      (node (ref "R_T_IMB") (pin "1") (pinfunction "1_1") (pintype "passive"))
      (node (ref "R_T_IPB") (pin "1") (pinfunction "1_1") (pintype "passive"))
    )
    (net (code "93") (name "Net-(C_V_A-Pad2)") (class "Default")
      (node (ref "C_V_A") (pin "2") (pinfunction "2_2") (pintype "passive"))
      (node (ref "R_V_IMA") (pin "1") (pinfunction "1_1") (pintype "passive"))
      (node (ref "R_V_IPA") (pin "1") (pinfunction "1_1") (pintype "passive"))
    )
    (net (code "94") (name "Net-(C_V_B-Pad2)") (class "Default")
      (node (ref "C_V_B") (pin "2") (pinfunction "2_2") (pintype "passive"))
      (node (ref "R_V_IMB") (pin "1") (pinfunction "1_1") (pintype "passive"))
      (node (ref "R_V_IPB") (pin "1") (pinfunction "1_1") (pintype "passive"))
    )
    (net (code "95") (name "Net-(LED_T_ON-PadK)") (class "Default")
      (node (ref "LED_T_ON") (pin "K") (pinfunction "K_K") (pintype "passive"))
      (node (ref "R_T_ON") (pin "2") (pinfunction "2_2") (pintype "passive"))
    )
    (net (code "96") (name "Net-(LED_V_ON-PadK)") (class "Default")
      (node (ref "LED_V_ON") (pin "K") (pinfunction "K_K") (pintype "passive"))
      (node (ref "R_V_ON") (pin "2") (pinfunction "2_2") (pintype "passive"))
    )
    (net (code "97") (name "Net-(T_LDO-SHDN)") (class "Default")
      (node (ref "T_LDO") (pin "7") (pinfunction "SHDN_7") (pintype "passive"))
      (node (ref "T_LDO_NMOS") (pin "3") (pinfunction "D_3") (pintype "passive"))
      (node (ref "T_LDO_PU") (pin "1") (pinfunction "1_1") (pintype "passive"))
    )
    (net (code "98") (name "Net-(V_LDO-SHDN)") (class "Default")
      (node (ref "V_LDO") (pin "7") (pinfunction "SHDN_7") (pintype "passive"))
      (node (ref "V_LDO_NMOS") (pin "3") (pinfunction "D_3") (pintype "passive"))
      (node (ref "V_LDO_PU") (pin "1") (pinfunction "1_1") (pintype "passive"))
    )
    (net (code "99") (name "unconnected-(T_LDO-ADJ-Pad2)") (class "Default")
      (node (ref "T_LDO") (pin "2") (pinfunction "ADJ_2") (pintype "passive"))
    )
    (net (code "100") (name "unconnected-(T_LDO-REF-Pad1)") (class "Default")
      (node (ref "T_LDO") (pin "1") (pinfunction "REF_1") (pintype "passive"))
    )
    (net (code "101") (name "unconnected-(Temperature-GPIO1-Pad39)") (class "Default")
      (node (ref "Temperature") (pin "39") (pinfunction "GPIO1_39") (pintype "passive"))
    )
    (net (code "102") (name "unconnected-(Temperature-GPIO2-Pad40)") (class "Default")
      (node (ref "Temperature") (pin "40") (pinfunction "GPIO2_40") (pintype "passive"))
    )
    (net (code "103") (name "unconnected-(Temperature-GPIO3-Pad41)") (class "Default")
      (node (ref "Temperature") (pin "41") (pinfunction "GPIO3_41") (pintype "passive"))
    )
    (net (code "104") (name "unconnected-(Temperature-GPIO4-Pad42)") (class "Default")
      (node (ref "Temperature") (pin "42") (pinfunction "GPIO4_42") (pintype "passive"))
    )
    (net (code "105") (name "unconnected-(Temperature-GPIO5-Pad43)") (class "Default")
      (node (ref "Temperature") (pin "43") (pinfunction "GPIO5_43") (pintype "passive"))
    )
    (net (code "106") (name "unconnected-(Temperature-GPIO6-Pad44)") (class "Default")
      (node (ref "Temperature") (pin "44") (pinfunction "GPIO6_44") (pintype "passive"))
    )
    (net (code "107") (name "unconnected-(Temperature-GPIO7-Pad45)") (class "Default")
      (node (ref "Temperature") (pin "45") (pinfunction "GPIO7_45") (pintype "passive"))
    )
    (net (code "108") (name "unconnected-(Temperature-GPIO8-Pad46)") (class "Default")
      (node (ref "Temperature") (pin "46") (pinfunction "GPIO8_46") (pintype "passive"))
    )
    (net (code "109") (name "unconnected-(Temperature-GPIO9-Pad47)") (class "Default")
      (node (ref "Temperature") (pin "47") (pinfunction "GPIO9_47") (pintype "passive"))
    )
    (net (code "110") (name "unconnected-(Temperature-S1-Pad37)") (class "Default")
      (node (ref "Temperature") (pin "37") (pinfunction "S1_37") (pintype "passive"))
    )
    (net (code "111") (name "unconnected-(Temperature-S2-Pad35)") (class "Default")
      (node (ref "Temperature") (pin "35") (pinfunction "S2_35") (pintype "passive"))
    )
    (net (code "112") (name "unconnected-(Temperature-S3-Pad33)") (class "Default")
      (node (ref "Temperature") (pin "33") (pinfunction "S3_33") (pintype "passive"))
    )
    (net (code "113") (name "unconnected-(Temperature-S4-Pad31)") (class "Default")
      (node (ref "Temperature") (pin "31") (pinfunction "S4_31") (pintype "passive"))
    )
    (net (code "114") (name "unconnected-(Temperature-S5-Pad29)") (class "Default")
      (node (ref "Temperature") (pin "29") (pinfunction "S5_29") (pintype "passive"))
    )
    (net (code "115") (name "unconnected-(Temperature-S6-Pad27)") (class "Default")
      (node (ref "Temperature") (pin "27") (pinfunction "S6_27") (pintype "passive"))
    )
    (net (code "116") (name "unconnected-(Temperature-S7-Pad25)") (class "Default")
      (node (ref "Temperature") (pin "25") (pinfunction "S7_25") (pintype "passive"))
    )
    (net (code "117") (name "unconnected-(Temperature-S8-Pad23)") (class "Default")
      (node (ref "Temperature") (pin "23") (pinfunction "S8_23") (pintype "passive"))
    )
    (net (code "118") (name "unconnected-(Temperature-S9-Pad21)") (class "Default")
      (node (ref "Temperature") (pin "21") (pinfunction "S9_21") (pintype "passive"))
    )
    (net (code "119") (name "unconnected-(Temperature-S10-Pad19)") (class "Default")
      (node (ref "Temperature") (pin "19") (pinfunction "S10_19") (pintype "passive"))
    )
    (net (code "120") (name "unconnected-(Temperature-S11-Pad17)") (class "Default")
      (node (ref "Temperature") (pin "17") (pinfunction "S11_17") (pintype "passive"))
    )
    (net (code "121") (name "unconnected-(Temperature-S12-Pad15)") (class "Default")
      (node (ref "Temperature") (pin "15") (pinfunction "S12_15") (pintype "passive"))
    )
    (net (code "122") (name "unconnected-(Temperature-S13-Pad13)") (class "Default")
      (node (ref "Temperature") (pin "13") (pinfunction "S13_13") (pintype "passive"))
    )
    (net (code "123") (name "unconnected-(Temperature-S14-Pad11)") (class "Default")
      (node (ref "Temperature") (pin "11") (pinfunction "S14_11") (pintype "passive"))
    )
    (net (code "124") (name "unconnected-(Temperature-S15-Pad9)") (class "Default")
      (node (ref "Temperature") (pin "9") (pinfunction "S15_9") (pintype "passive"))
    )
    (net (code "125") (name "unconnected-(Temperature-S16-Pad7)") (class "Default")
      (node (ref "Temperature") (pin "7") (pinfunction "S16_7") (pintype "passive"))
    )
    (net (code "126") (name "unconnected-(Temperature-S17-Pad5)") (class "Default")
      (node (ref "Temperature") (pin "5") (pinfunction "S17_5") (pintype "passive"))
    )
    (net (code "127") (name "unconnected-(Temperature-S18-Pad3)") (class "Default")
      (node (ref "Temperature") (pin "3") (pinfunction "S18_3") (pintype "passive"))
    )
    (net (code "128") (name "unconnected-(Temperature-SDI(NC)-Pad53)") (class "Default")
      (node (ref "Temperature") (pin "53") (pinfunction "SDI(NC)_53") (pintype "passive"))
    )
    (net (code "129") (name "unconnected-(Temperature-SDO(NC)-Pad54)") (class "Default")
      (node (ref "Temperature") (pin "54") (pinfunction "SDO(NC)_54") (pintype "passive"))
    )
    (net (code "130") (name "unconnected-(V_LDO-ADJ-Pad2)") (class "Default")
      (node (ref "V_LDO") (pin "2") (pinfunction "ADJ_2") (pintype "passive"))
    )
    (net (code "131") (name "unconnected-(V_LDO-REF-Pad1)") (class "Default")
      (node (ref "V_LDO") (pin "1") (pinfunction "REF_1") (pintype "passive"))
    )
    (net (code "132") (name "unconnected-(Voltage-GPIO1-Pad39)") (class "Default")
      (node (ref "Voltage") (pin "39") (pinfunction "GPIO1_39") (pintype "passive"))
    )
    (net (code "133") (name "unconnected-(Voltage-GPIO2-Pad40)") (class "Default")
      (node (ref "Voltage") (pin "40") (pinfunction "GPIO2_40") (pintype "passive"))
    )
    (net (code "134") (name "unconnected-(Voltage-GPIO3-Pad41)") (class "Default")
      (node (ref "Voltage") (pin "41") (pinfunction "GPIO3_41") (pintype "passive"))
    )
    (net (code "135") (name "unconnected-(Voltage-GPIO4-Pad42)") (class "Default")
      (node (ref "Voltage") (pin "42") (pinfunction "GPIO4_42") (pintype "passive"))
    )
    (net (code "136") (name "unconnected-(Voltage-GPIO5-Pad43)") (class "Default")
      (node (ref "Voltage") (pin "43") (pinfunction "GPIO5_43") (pintype "passive"))
    )
    (net (code "137") (name "unconnected-(Voltage-GPIO6-Pad44)") (class "Default")
      (node (ref "Voltage") (pin "44") (pinfunction "GPIO6_44") (pintype "passive"))
    )
    (net (code "138") (name "unconnected-(Voltage-GPIO7-Pad45)") (class "Default")
      (node (ref "Voltage") (pin "45") (pinfunction "GPIO7_45") (pintype "passive"))
    )
    (net (code "139") (name "unconnected-(Voltage-GPIO8-Pad46)") (class "Default")
      (node (ref "Voltage") (pin "46") (pinfunction "GPIO8_46") (pintype "passive"))
    )
    (net (code "140") (name "unconnected-(Voltage-GPIO9-Pad47)") (class "Default")
      (node (ref "Voltage") (pin "47") (pinfunction "GPIO9_47") (pintype "passive"))
    )
    (net (code "141") (name "unconnected-(Voltage-S12-Pad15)") (class "Default")
      (node (ref "Voltage") (pin "15") (pinfunction "S12_15") (pintype "passive"))
    )
    (net (code "142") (name "unconnected-(Voltage-S18-Pad3)") (class "Default")
      (node (ref "Voltage") (pin "3") (pinfunction "S18_3") (pintype "passive"))
    )
  )
)
